# IO_Power_Supply.net
KiCad netlist of a schematic drawn in Altium Designer
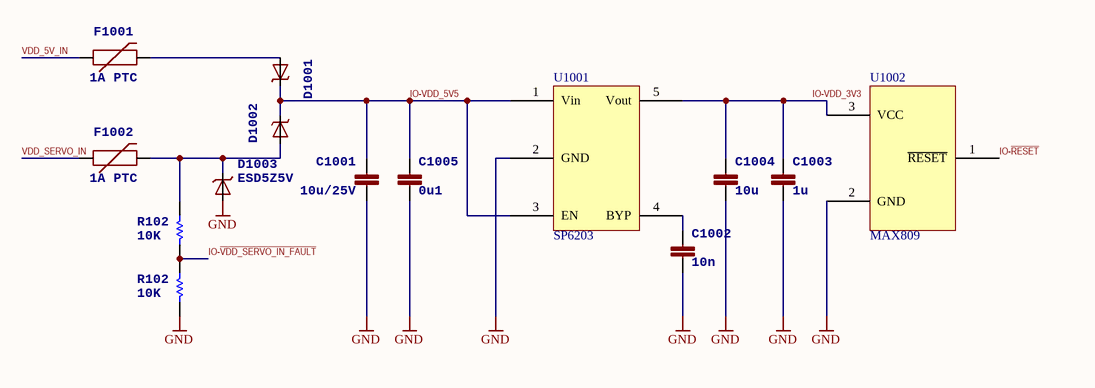
[diagram p0: IO Power Supply.SchDoc]

(export (version "E")
  (design (tool "Eeschema 10.0.6"))
  (components
    (comp (ref "C1001")
      (value "10u/25V")
      (footprint "0805-CAP")
      (description "<b>Capacitor</b>\nStandard 0603 ceramic capacitor, and 0.1\" leaded capacitor.")
      (fields
        (field (name "PARTNO") "CL21A106KAYNNNE")
        (field (name ">NAME") "C1001")
        (field (name ">VALUE") "10u/25V")
      )
      (libsource (lib "pixhawk2") (part "CAP0805"))
    )
    (comp (ref "C1002")
      (value "10n")
      (footprint "0603-CAP")
      (description "<b>Capacitor</b>\nStandard 0603 ceramic capacitor, and 0.1\" leaded capacitor.")
      (fields
        (field (name "PARTNO") "CC0402ZRY5V7BB104")
        (field (name ">NAME") "C1002")
        (field (name ">VALUE") "10n")
      )
      (libsource (lib "pixhawk2") (part "CAP0402"))
    )
    (comp (ref "C1003")
      (value "1u")
      (footprint "0603-CAP")
      (description "<b>Capacitor</b>\nStandard 0603 ceramic capacitor, and 0.1\" leaded capacitor.")
      (fields
        (field (name "PARTNO") "CC0603ZRY5V7BB105")
        (field (name ">NAME") "C1003")
        (field (name ">VALUE") "1u")
      )
      (libsource (lib "pixhawk2") (part "CAP0603"))
    )
    (comp (ref "C1004")
      (value "10u")
      (footprint "0805-CAP")
      (description "<b>Capacitor</b>\nStandard 0603 ceramic capacitor, and 0.1\" leaded capacitor.")
      (fields
        (field (name "PARTNO") "C1608X5R1A106K080AC")
        (field (name ">NAME") "C1004")
        (field (name ">VALUE") "10u")
      )
      (libsource (lib "pixhawk2") (part "CAP0603"))
    )
    (comp (ref "C1005")
      (value "0u1")
      (footprint "0603-CAP")
      (description "<b>Capacitor</b>\nStandard 0603 ceramic capacitor, and 0.1\" leaded capacitor.")
      (fields
        (field (name "PARTNO") "CC0402ZRY5V7BB104")
        (field (name ">NAME") "C1005")
        (field (name ">VALUE") "0u1")
      )
      (libsource (lib "pixhawk2") (part "CAP0402"))
    )
    (comp (ref "D1001")
      (value "SS14 SOD323")
      (footprint "SOD323")
      (description "Schottky barrier diode in DO214AC, e.g. Fairchild SS14.")
      (libsource (lib "pixhawk2") (part "DIODE-SCHOTTKY_MSMP"))
    )
    (comp (ref "D1002")
      (value "SS14 SOD323")
      (footprint "SOD323")
      (description "Schottky barrier diode in DO214AC, e.g. Fairchild SS14.")
      (libsource (lib "pixhawk2") (part "DIODE-SCHOTTKY_MSMP"))
    )
    (comp (ref "D1003")
      (value "ESD5Z5V")
      (footprint "SOD523")
      (libsource (lib "pixhawk2") (part "DIODE-TVS"))
    )
    (comp (ref "F1001")
      (value "1A PTC")
      (footprint "PTC-1206")
      (description "<b>Resettable Fuse PTC</b>\nResettable Fuse. Spark Fun Electronics SKU : COM-08357")
      (fields (field (name ">NAME") "F1001") (field (name ">VALUE") "1A PTC"))
      (libsource (lib "pixhawk2") (part "PTCSMD"))
    )
    (comp (ref "F1002")
      (value "1A PTC")
      (footprint "PTC-1206")
      (description "<b>Resettable Fuse PTC</b>\nResettable Fuse. Spark Fun Electronics SKU : COM-08357")
      (fields (field (name ">NAME") "F1002") (field (name ">VALUE") "1A PTC"))
      (libsource (lib "pixhawk2") (part "PTCSMD"))
    )
    (comp (ref "R1001")
      (value "10K")
      (footprint "0603-RES")
      (fields
        (field (name "PARTNO") "RC0402FR-0710KL")
        (field (name ">NAME") "R102")
        (field (name ">VALUE") "10K")
      )
      (libsource (lib "PX4") (part "RESISTOR0402-RES"))
    )
    (comp (ref "R1002")
      (value "10K")
      (footprint "0603-RES")
      (fields
        (field (name "PARTNO") "RC0402FR-0710KL")
        (field (name ">NAME") "R102")
        (field (name ">VALUE") "10K")
      )
      (libsource (lib "PX4") (part "RESISTOR0402-RES"))
    )
    (comp (ref "U1001")
      (value "SP6203")
      (footprint "SOT23-5")
      (description "LDO with reset")
      (libsource (lib "PX4") (part "SP6203"))
    )
    (comp (ref "U1002") (value "MAX809") (footprint "SOT-23B_N") (libsource (lib "PX4") (part "MAX809")))
  )
  (nets
    (net (code "1") (name "/IO-VDD_3V3") (class "Default")
      (node (ref "C1003") (pin "P$1") (pinfunction "1_P$1") (pintype "passive"))
      (node (ref "C1004") (pin "P$1") (pinfunction "1_P$1") (pintype "passive"))
      (node (ref "U1001") (pin "5") (pinfunction "Vout_5") (pintype "passive"))
      (node (ref "U1002") (pin "3") (pinfunction "VCC_3") (pintype "passive"))
    )
    (net (code "2") (name "/IO-VDD_5V5") (class "Default")
      (node (ref "C1001") (pin "P$1") (pinfunction "1_P$1") (pintype "passive"))
      (node (ref "C1005") (pin "P$1") (pinfunction "1_P$1") (pintype "passive"))
      (node (ref "D1001") (pin "C") (pinfunction "C_C") (pintype "passive"))
      (node (ref "D1002") (pin "C") (pinfunction "C_C") (pintype "passive"))
      (node (ref "U1001") (pin "1") (pinfunction "Vin_1") (pintype "passive"))
      (node (ref "U1001") (pin "3") (pinfunction "EN_3") (pintype "passive"))
    )
    (net (code "3") (name "/IO-~{RESET}") (class "Default")
      (node (ref "U1002") (pin "1") (pinfunction "~{RESET}_1") (pintype "passive"))
    )
    (net (code "4") (name "/IO-~{VDD_SERVO_IN_FAULT}") (class "Default")
      (node (ref "R1001") (pin "P$1") (pinfunction "1_P$1") (pintype "passive"))
      (node (ref "R1002") (pin "P$2") (pinfunction "2_P$2") (pintype "passive"))
    )
    (net (code "5") (name "/VDD_5V_IN") (class "Default")
      (node (ref "F1001") (pin "1") (pinfunction "1_1") (pintype "passive"))
    )
    (net (code "6") (name "/VDD_SERVO_IN") (class "Default")
      (node (ref "F1002") (pin "1") (pinfunction "1_1") (pintype "passive"))
    )
    (net (code "7") (name "GND") (class "Default")
      (node (ref "C1001") (pin "P$2") (pinfunction "2_P$2") (pintype "passive"))
      (node (ref "C1002") (pin "P$2") (pinfunction "2_P$2") (pintype "passive"))
      (node (ref "C1003") (pin "P$2") (pinfunction "2_P$2") (pintype "passive"))
      (node (ref "C1004") (pin "P$2") (pinfunction "2_P$2") (pintype "passive"))
      (node (ref "C1005") (pin "P$2") (pinfunction "2_P$2") (pintype "passive"))
      (node (ref "D1003") (pin "A") (pinfunction "A_A") (pintype "passive"))
      (node (ref "R1002") (pin "P$1") (pinfunction "1_P$1") (pintype "passive"))
      (node (ref "U1001") (pin "2") (pinfunction "GND_2") (pintype "passive"))
      (node (ref "U1002") (pin "2") (pinfunction "GND_2") (pintype "passive"))
    )
    (net (code "8") (name "Net-(C1002-1)") (class "Default")
      (node (ref "C1002") (pin "P$1") (pinfunction "1_P$1") (pintype "passive"))
      (node (ref "U1001") (pin "4") (pinfunction "BYP_4") (pintype "passive"))
    )
    (net (code "9") (name "Net-(D1001-PadA)") (class "Default")
      (node (ref "D1001") (pin "A") (pinfunction "A_A") (pintype "passive"))
      (node (ref "F1001") (pin "2") (pinfunction "2_2") (pintype "passive"))
    )
    (net (code "10") (name "Net-(R1001-2)") (class "Default")
      (node (ref "D1002") (pin "A") (pinfunction "A_A") (pintype "passive"))
      (node (ref "D1003") (pin "C") (pinfunction "C_C") (pintype "passive"))
      (node (ref "F1002") (pin "2") (pinfunction "2_2") (pintype "passive"))
      (node (ref "R1001") (pin "P$2") (pinfunction "2_P$2") (pintype "passive"))
    )
  )
)
